# Regulators2.net
KiCad netlist of a schematic drawn in Altium Designer
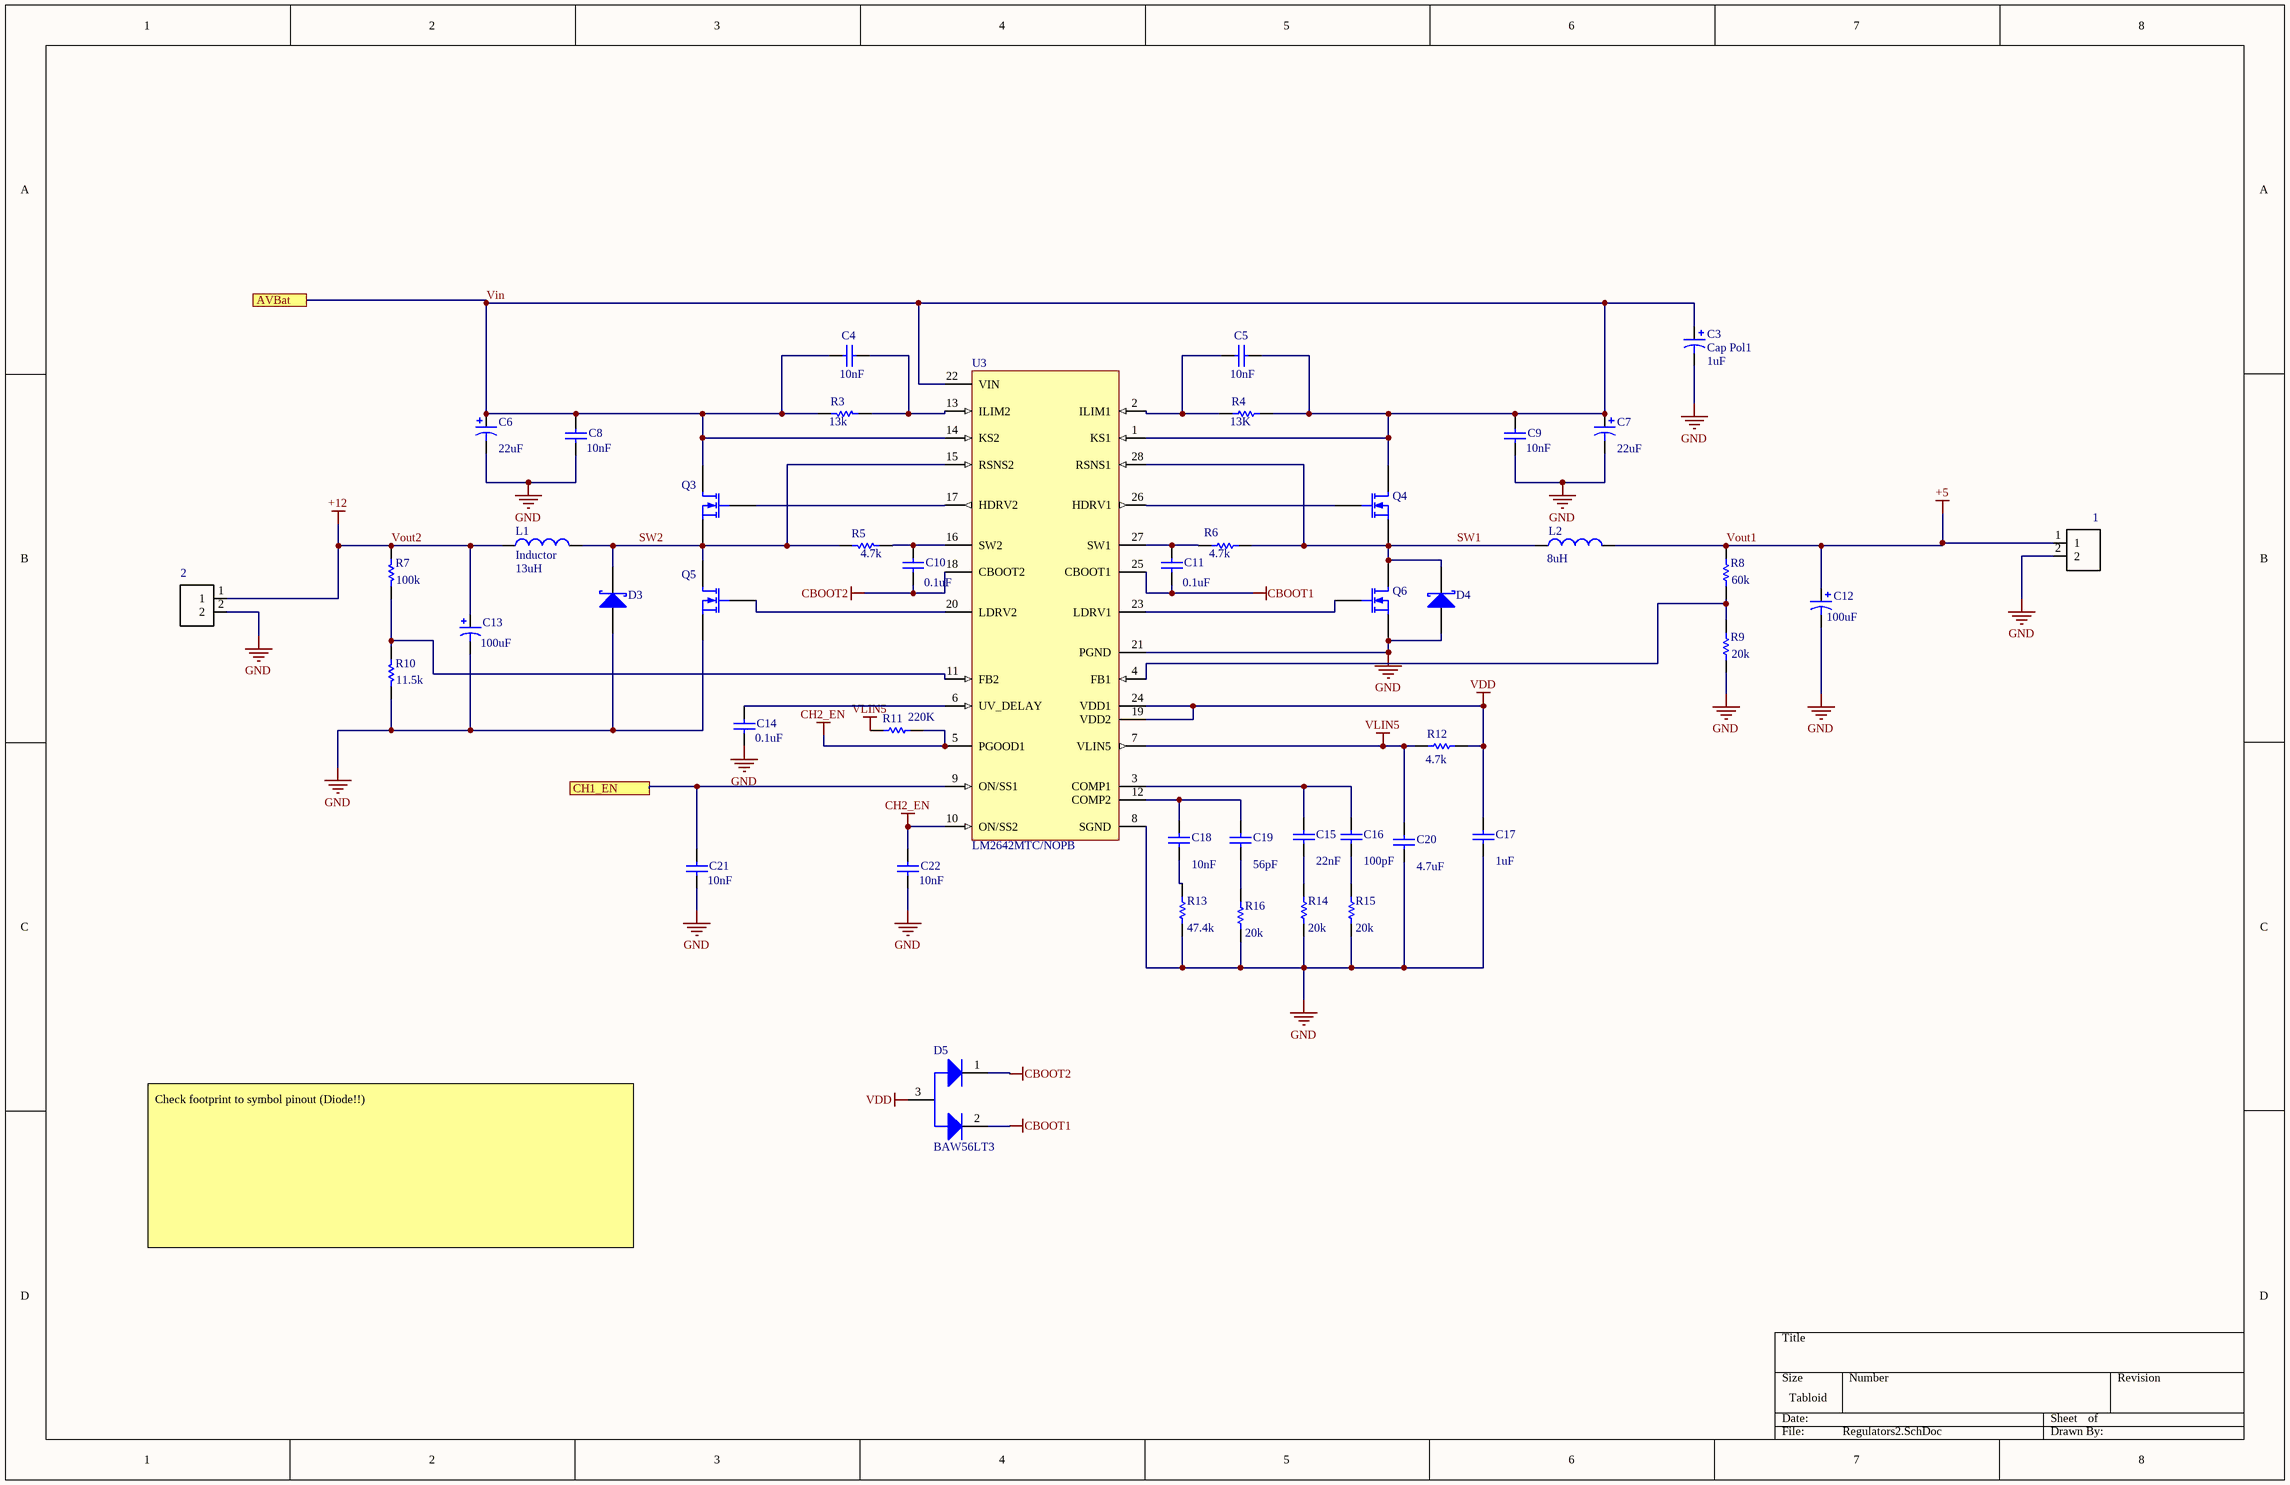
[diagram p0: Regulators2.SchDoc]

(export (version "E")
  (design (tool "Eeschema 10.0.6"))
  (components
    (comp (ref "1")
      (value "282836-2")
      (footprint "*CONN_282836-2")
      (description "Connector, Terminal Block; Wire Receptacle; 2 Pos.; 16-30 AWG; 0.197 in. CL; Sid")
      (fields (field (name "DIGI-KEY_PART_NUMBER") "A98076-ND") (field (name "MF") "TE Connectivity"))
      (libsource (lib "TerminalBlockx2") (part "282836-2"))
    )
    (comp (ref "2")
      (value "282836-2")
      (footprint "*CONN_282836-2")
      (description "Connector, Terminal Block; Wire Receptacle; 2 Pos.; 16-30 AWG; 0.197 in. CL; Sid")
      (fields (field (name "DIGI-KEY_PART_NUMBER") "A98076-ND") (field (name "MF") "TE Connectivity"))
      (libsource (lib "TerminalBlockx2") (part "282836-2"))
    )
    (comp (ref "C3")
      (value "Cap Pol1")
      (footprint "1u50VcapE")
      (description "Polarized Capacitor (Radial)")
      (fields (field (name "ALTIUM_VALUE") "1uF") (field (name "PUBLISHER") "Altium Limited"))
      (libsource (lib "") (part "Cap Pol1_1"))
    )
    (comp (ref "C4")
      (value "10nF")
      (footprint "1608[0603]")
      (description "Capacitor")
      (fields (field (name "Comment") "Cap") (field (name "PUBLISHER") "Altium Limited"))
      (libsource (lib "Miscellaneous Devices") (part "Cap"))
    )
    (comp (ref "C5")
      (value "10nF")
      (footprint "1608[0603]")
      (description "Capacitor")
      (fields (field (name "Comment") "Cap") (field (name "PUBLISHER") "Altium Limited"))
      (libsource (lib "Miscellaneous Devices") (part "Cap"))
    )
    (comp (ref "C6")
      (value "22uF")
      (footprint "22u16VcapE")
      (description "Polarized Capacitor (Radial)")
      (fields (field (name "Comment") "Cap Pol1") (field (name "PUBLISHER") "Altium Limited"))
      (libsource (lib "Miscellaneous Devices") (part "Cap Pol1"))
    )
    (comp (ref "C7")
      (value "22uF")
      (footprint "22u16VcapE")
      (description "Polarized Capacitor (Radial)")
      (fields (field (name "Comment") "Cap Pol1") (field (name "PUBLISHER") "Altium Limited"))
      (libsource (lib "") (part "Cap Pol1_1"))
    )
    (comp (ref "C8")
      (value "10nF")
      (footprint "1608[0603]")
      (description "Capacitor")
      (fields (field (name "Comment") "Cap") (field (name "PUBLISHER") "Altium Limited"))
      (libsource (lib "Miscellaneous Devices") (part "Cap"))
    )
    (comp (ref "C9")
      (value "10nF")
      (footprint "1608[0603]")
      (description "Capacitor")
      (fields (field (name "Comment") "Cap") (field (name "PUBLISHER") "Altium Limited"))
      (libsource (lib "Miscellaneous Devices") (part "Cap"))
    )
    (comp (ref "C10")
      (value "0.1uF")
      (footprint "1608[0603]")
      (description "Capacitor")
      (fields (field (name "Comment") "Cap") (field (name "PUBLISHER") "Altium Limited"))
      (libsource (lib "Miscellaneous Devices") (part "Cap"))
    )
    (comp (ref "C11")
      (value "0.1uF")
      (footprint "1608[0603]")
      (description "Capacitor")
      (fields (field (name "Comment") "Cap") (field (name "PUBLISHER") "Altium Limited"))
      (libsource (lib "Miscellaneous Devices") (part "Cap"))
    )
    (comp (ref "C12")
      (value "100uF")
      (footprint "*CAPAE660X800N")
      (description "Polarized Capacitor (Radial)")
      (fields (field (name "Comment") "Cap Pol1") (field (name "PUBLISHER") "Altium Limited"))
      (libsource (lib "") (part "Cap Pol1_1"))
    )
    (comp (ref "C13")
      (value "100uF")
      (footprint "*CAPAE660X800N")
      (description "Polarized Capacitor (Radial)")
      (fields (field (name "Comment") "Cap Pol1") (field (name "PUBLISHER") "Altium Limited"))
      (libsource (lib "Miscellaneous Devices") (part "Cap Pol1"))
    )
    (comp (ref "C14")
      (value "0.1uF")
      (footprint "1608[0603]")
      (description "Capacitor")
      (fields (field (name "Comment") "Cap") (field (name "PUBLISHER") "Altium Limited"))
      (libsource (lib "Miscellaneous Devices") (part "Cap"))
    )
    (comp (ref "C15")
      (value "22nF")
      (footprint "1608[0603]")
      (description "Capacitor")
      (fields (field (name "Comment") "Cap") (field (name "PUBLISHER") "Altium Limited"))
      (libsource (lib "Miscellaneous Devices") (part "Cap"))
    )
    (comp (ref "C16")
      (value "100pF")
      (footprint "1608[0603]")
      (description "Capacitor")
      (fields (field (name "Comment") "Cap") (field (name "PUBLISHER") "Altium Limited"))
      (libsource (lib "Miscellaneous Devices") (part "Cap"))
    )
    (comp (ref "C17")
      (value "1uF")
      (footprint "1608[0603]")
      (description "Capacitor")
      (fields (field (name "Comment") "Cap") (field (name "PUBLISHER") "Altium Limited"))
      (libsource (lib "Miscellaneous Devices") (part "Cap"))
    )
    (comp (ref "C18")
      (value "10nF")
      (footprint "1608[0603]")
      (description "Capacitor")
      (fields (field (name "Comment") "Cap") (field (name "PUBLISHER") "Altium Limited"))
      (libsource (lib "Miscellaneous Devices") (part "Cap"))
    )
    (comp (ref "C19")
      (value "56pF")
      (footprint "1608[0603]")
      (description "Capacitor")
      (fields (field (name "Comment") "Cap") (field (name "PUBLISHER") "Altium Limited"))
      (libsource (lib "Miscellaneous Devices") (part "Cap"))
    )
    (comp (ref "C20")
      (value "4.7uF")
      (footprint "1608[0603]")
      (description "Capacitor")
      (fields (field (name "Comment") "Cap") (field (name "PUBLISHER") "Altium Limited"))
      (libsource (lib "Miscellaneous Devices") (part "Cap"))
    )
    (comp (ref "C21")
      (value "10nF")
      (footprint "1608[0603]")
      (description "Capacitor")
      (fields (field (name "Comment") "Cap") (field (name "PUBLISHER") "Altium Limited"))
      (libsource (lib "Miscellaneous Devices") (part "Cap"))
    )
    (comp (ref "C22")
      (value "10nF")
      (footprint "1608[0603]")
      (description "Capacitor")
      (fields (field (name "Comment") "Cap") (field (name "PUBLISHER") "Altium Limited"))
      (libsource (lib "Miscellaneous Devices") (part "Cap"))
    )
    (comp (ref "D3")
      (value "Diode MBRS140t3")
      (footprint "*DIOM5227X270N_S1M(Primary)")
      (description "Schottky Rectifier")
      (fields (field (name "PUBLISHER") "Altium Limited"))
      (libsource (lib "Miscellaneous Devices") (part "Diode 18TQ045"))
    )
    (comp (ref "D4")
      (value "Diode MBRS140t3")
      (footprint "*DIOM5227X270N_S1M(Primary)")
      (description "Schottky Rectifier")
      (fields (field (name "PUBLISHER") "Altium Limited"))
      (libsource (lib "Miscellaneous Devices") (part "Diode 18TQ045"))
    )
    (comp (ref "D5")
      (value "BAW56LT3")
      (footprint "ONSC-SOT-23-3-318-08_V")
      (description "Dual Switching Diodes, Common Anode, 3-Pin SOT-23, Tape and Reel")
      (fields (field (name "MANUFACTURER") "On Semiconductor"))
      (libsource (lib "ON Semi Small Signal Switching Diodes") (part "BAW56LT3"))
    )
    (comp (ref "L1")
      (value "Inductor")
      (footprint "Inductor")
      (fields (field (name "ALTIUM_VALUE") "13uH") (field (name "PUBLISHER") "Altium Limited"))
      (libsource (lib "Miscellaneous Devices") (part "Inductor"))
    )
    (comp (ref "L2")
      (value "8uH")
      (footprint "Inductor")
      (description "Inductor")
      (fields (field (name "PUBLISHER") "Altium Limited"))
      (libsource (lib "Miscellaneous Devices") (part "Inductor"))
    )
    (comp (ref "Q3")
      (value "MOSFET-N")
      (footprint "SO8_L")
      (description "N-Channel MOSFET")
      (fields (field (name "PUBLISHER") "Altium Limited"))
      (libsource (lib "Miscellaneous Devices") (part "MOSFET-N"))
    )
    (comp (ref "Q4")
      (value "MOSFET-N")
      (footprint "SO8_L")
      (description "N-Channel MOSFET")
      (fields (field (name "PUBLISHER") "Altium Limited"))
      (libsource (lib "Miscellaneous Devices") (part "MOSFET-N"))
    )
    (comp (ref "Q5")
      (value "MOSFET-N")
      (footprint "SO8_L")
      (description "N-Channel MOSFET")
      (fields (field (name "PUBLISHER") "Altium Limited"))
      (libsource (lib "Miscellaneous Devices") (part "MOSFET-N"))
    )
    (comp (ref "Q6")
      (value "MOSFET-N")
      (footprint "SO8_L")
      (description "N-Channel MOSFET")
      (fields (field (name "PUBLISHER") "Altium Limited"))
      (libsource (lib "Miscellaneous Devices") (part "MOSFET-N"))
    )
    (comp (ref "R3")
      (value "13k")
      (footprint "1608[0603]")
      (description "Resistor")
      (fields (field (name "Comment") "Res1") (field (name "PUBLISHER") "Altium Limited"))
      (libsource (lib "Miscellaneous Devices") (part "Res1"))
    )
    (comp (ref "R4")
      (value "13K")
      (footprint "1608[0603]")
      (description "Resistor")
      (fields (field (name "Comment") "Res1") (field (name "PUBLISHER") "Altium Limited"))
      (libsource (lib "Miscellaneous Devices") (part "Res1"))
    )
    (comp (ref "R5")
      (value "4.7k")
      (footprint "1608[0603]")
      (description "Resistor")
      (fields (field (name "Comment") "Res1") (field (name "PUBLISHER") "Altium Limited"))
      (libsource (lib "Miscellaneous Devices") (part "Res1"))
    )
    (comp (ref "R6")
      (value "4.7k")
      (footprint "1608[0603]")
      (description "Resistor")
      (fields (field (name "Comment") "Res1") (field (name "PUBLISHER") "Altium Limited"))
      (libsource (lib "Miscellaneous Devices") (part "Res1"))
    )
    (comp (ref "R7")
      (value "100k")
      (footprint "1608[0603]")
      (description "Resistor")
      (fields (field (name "Comment") "Res1") (field (name "PUBLISHER") "Altium Limited"))
      (libsource (lib "Miscellaneous Devices") (part "Res1"))
    )
    (comp (ref "R8")
      (value "60k")
      (footprint "1608[0603]")
      (description "Resistor")
      (fields (field (name "Comment") "Res1") (field (name "PUBLISHER") "Altium Limited"))
      (libsource (lib "Miscellaneous Devices") (part "Res1"))
    )
    (comp (ref "R9")
      (value "20k")
      (footprint "1608[0603]")
      (description "Resistor")
      (fields (field (name "Comment") "Res1") (field (name "PUBLISHER") "Altium Limited"))
      (libsource (lib "Miscellaneous Devices") (part "Res1"))
    )
    (comp (ref "R10")
      (value "11.5k")
      (footprint "1608[0603]")
      (description "Resistor")
      (fields (field (name "Comment") "Res1") (field (name "PUBLISHER") "Altium Limited"))
      (libsource (lib "Miscellaneous Devices") (part "Res1"))
    )
    (comp (ref "R11")
      (value "220K")
      (footprint "1608[0603]")
      (description "Resistor")
      (fields (field (name "Comment") "Res1") (field (name "PUBLISHER") "Altium Limited"))
      (libsource (lib "Miscellaneous Devices") (part "Res1"))
    )
    (comp (ref "R12")
      (value "4.7k")
      (footprint "1608[0603]")
      (description "Resistor")
      (fields (field (name "Comment") "Res1") (field (name "PUBLISHER") "Altium Limited"))
      (libsource (lib "Miscellaneous Devices") (part "Res1"))
    )
    (comp (ref "R13")
      (value "47.4k")
      (footprint "1608[0603]")
      (description "Resistor")
      (fields (field (name "Comment") "Res1") (field (name "PUBLISHER") "Altium Limited"))
      (libsource (lib "Miscellaneous Devices") (part "Res1"))
    )
    (comp (ref "R14")
      (value "20k")
      (footprint "1608[0603]")
      (description "Resistor")
      (fields (field (name "Comment") "Res1") (field (name "PUBLISHER") "Altium Limited"))
      (libsource (lib "Miscellaneous Devices") (part "Res1"))
    )
    (comp (ref "R15")
      (value "20k")
      (footprint "1608[0603]")
      (description "Resistor")
      (fields (field (name "Comment") "Res1") (field (name "PUBLISHER") "Altium Limited"))
      (libsource (lib "Miscellaneous Devices") (part "Res1"))
    )
    (comp (ref "R16")
      (value "20k")
      (footprint "1608[0603]")
      (description "Resistor")
      (fields (field (name "Comment") "Res1") (field (name "PUBLISHER") "Altium Limited"))
      (libsource (lib "Miscellaneous Devices") (part "Res1"))
    )
    (comp (ref "U3")
      (value "LM2642MTC/NOPB")
      (footprint "MTC28_N")
      (description "Two-Phase Synchronous Step-Down Switching Controller, 28-pin TSSOP, Pb-Free")
      (fields (field (name "MANUFACTURER") "National Semiconductor"))
      (libsource (lib "National Semiconductor Switcher") (part "LM2642MTC/NOPB"))
    )
  )
  (nets
    (net (code "1") (name "+5") (class "Default")
      (node (ref "1") (pin "1") (pinfunction "1_1") (pintype "passive"))
      (node (ref "C12") (pin "1") (pinfunction "1_1") (pintype "passive"))
      (node (ref "L2") (pin "2") (pinfunction "2_2") (pintype "passive"))
      (node (ref "R8") (pin "2") (pinfunction "2_2") (pintype "passive"))
    )
    (net (code "2") (name "+12") (class "Default")
      (node (ref "2") (pin "1") (pinfunction "1_1") (pintype "passive"))
      (node (ref "C13") (pin "1") (pinfunction "1_1") (pintype "passive"))
      (node (ref "L1") (pin "1") (pinfunction "1_1") (pintype "passive"))
      (node (ref "R7") (pin "2") (pinfunction "2_2") (pintype "passive"))
    )
    (net (code "3") (name "/CH1_EN") (class "Default")
      (node (ref "C21") (pin "2") (pinfunction "2_2") (pintype "passive"))
      (node (ref "U3") (pin "9") (pinfunction "ON/SS1_9") (pintype "input"))
    )
    (net (code "4") (name "/SW1") (class "Default")
      (node (ref "D4") (pin "1") (pinfunction "K_1") (pintype "passive"))
      (node (ref "L2") (pin "1") (pinfunction "1_1") (pintype "passive"))
      (node (ref "Q4") (pin "3") (pinfunction "S_3") (pintype "passive"))
      (node (ref "Q6") (pin "1") (pinfunction "D_1") (pintype "passive"))
      (node (ref "R6") (pin "2") (pinfunction "2_2") (pintype "passive"))
      (node (ref "U3") (pin "28") (pinfunction "RSNS1_28") (pintype "input"))
    )
    (net (code "5") (name "/SW2") (class "Default")
      (node (ref "D3") (pin "1") (pinfunction "K_1") (pintype "passive"))
      (node (ref "L1") (pin "2") (pinfunction "2_2") (pintype "passive"))
      (node (ref "Q3") (pin "3") (pinfunction "S_3") (pintype "passive"))
      (node (ref "Q5") (pin "1") (pinfunction "D_1") (pintype "passive"))
      (node (ref "R5") (pin "2") (pinfunction "2_2") (pintype "passive"))
      (node (ref "U3") (pin "15") (pinfunction "RSNS2_15") (pintype "input"))
    )
    (net (code "6") (name "/Vin") (class "Default")
      (node (ref "C3") (pin "1") (pinfunction "1_1") (pintype "passive"))
      (node (ref "C4") (pin "2") (pinfunction "2_2") (pintype "passive"))
      (node (ref "C5") (pin "2") (pinfunction "2_2") (pintype "passive"))
      (node (ref "C6") (pin "1") (pinfunction "1_1") (pintype "passive"))
      (node (ref "C7") (pin "1") (pinfunction "1_1") (pintype "passive"))
      (node (ref "C8") (pin "2") (pinfunction "2_2") (pintype "passive"))
      (node (ref "C9") (pin "2") (pinfunction "2_2") (pintype "passive"))
      (node (ref "Q3") (pin "1") (pinfunction "D_1") (pintype "passive"))
      (node (ref "Q4") (pin "1") (pinfunction "D_1") (pintype "passive"))
      (node (ref "R3") (pin "2") (pinfunction "2_2") (pintype "passive"))
      (node (ref "R4") (pin "2") (pinfunction "2_2") (pintype "passive"))
      (node (ref "U3") (pin "1") (pinfunction "KS1_1") (pintype "input"))
      (node (ref "U3") (pin "14") (pinfunction "KS2_14") (pintype "input"))
      (node (ref "U3") (pin "22") (pinfunction "VIN_22") (pintype "power_in"))
    )
    (net (code "7") (name "CBOOT1") (class "Default")
      (node (ref "C11") (pin "1") (pinfunction "1_1") (pintype "passive"))
      (node (ref "D5") (pin "2") (pinfunction "K2_2") (pintype "passive"))
      (node (ref "U3") (pin "25") (pinfunction "CBOOT1_25") (pintype "passive"))
    )
    (net (code "8") (name "CBOOT2") (class "Default")
      (node (ref "C10") (pin "1") (pinfunction "1_1") (pintype "passive"))
      (node (ref "D5") (pin "1") (pinfunction "K1_1") (pintype "passive"))
      (node (ref "U3") (pin "18") (pinfunction "CBOOT2_18") (pintype "passive"))
    )
    (net (code "9") (name "CH2_EN") (class "Default")
      (node (ref "C22") (pin "2") (pinfunction "2_2") (pintype "passive"))
      (node (ref "R11") (pin "2") (pinfunction "2_2") (pintype "passive"))
      (node (ref "U3") (pin "10") (pinfunction "ON/SS2_10") (pintype "input"))
      (node (ref "U3") (pin "5") (pinfunction "PGOOD1_5") (pintype "open_collector"))
    )
    (net (code "10") (name "GND") (class "Default")
      (node (ref "1") (pin "2") (pinfunction "2_2") (pintype "passive"))
      (node (ref "2") (pin "2") (pinfunction "2_2") (pintype "passive"))
      (node (ref "C12") (pin "2") (pinfunction "2_2") (pintype "passive"))
      (node (ref "C13") (pin "2") (pinfunction "2_2") (pintype "passive"))
      (node (ref "C14") (pin "1") (pinfunction "1_1") (pintype "passive"))
      (node (ref "C17") (pin "1") (pinfunction "1_1") (pintype "passive"))
      (node (ref "C20") (pin "1") (pinfunction "1_1") (pintype "passive"))
      (node (ref "C21") (pin "1") (pinfunction "1_1") (pintype "passive"))
      (node (ref "C22") (pin "1") (pinfunction "1_1") (pintype "passive"))
      (node (ref "C3") (pin "2") (pinfunction "2_2") (pintype "passive"))
      (node (ref "C6") (pin "2") (pinfunction "2_2") (pintype "passive"))
      (node (ref "C7") (pin "2") (pinfunction "2_2") (pintype "passive"))
      (node (ref "C8") (pin "1") (pinfunction "1_1") (pintype "passive"))
      (node (ref "C9") (pin "1") (pinfunction "1_1") (pintype "passive"))
      (node (ref "D3") (pin "3") (pinfunction "A_3") (pintype "passive"))
      (node (ref "D4") (pin "3") (pinfunction "A_3") (pintype "passive"))
      (node (ref "Q5") (pin "3") (pinfunction "S_3") (pintype "passive"))
      (node (ref "Q6") (pin "3") (pinfunction "S_3") (pintype "passive"))
      (node (ref "R10") (pin "1") (pinfunction "1_1") (pintype "passive"))
      (node (ref "R13") (pin "1") (pinfunction "1_1") (pintype "passive"))
      (node (ref "R14") (pin "1") (pinfunction "1_1") (pintype "passive"))
      (node (ref "R15") (pin "1") (pinfunction "1_1") (pintype "passive"))
      (node (ref "R16") (pin "1") (pinfunction "1_1") (pintype "passive"))
      (node (ref "R9") (pin "1") (pinfunction "1_1") (pintype "passive"))
      (node (ref "U3") (pin "21") (pinfunction "PGND_21") (pintype "power_in"))
      (node (ref "U3") (pin "8") (pinfunction "SGND_8") (pintype "power_in"))
    )
    (net (code "11") (name "Net-(C15-Pad1)") (class "Default")
      (node (ref "C15") (pin "1") (pinfunction "1_1") (pintype "passive"))
      (node (ref "R14") (pin "2") (pinfunction "2_2") (pintype "passive"))
    )
    (net (code "12") (name "Net-(C16-Pad1)") (class "Default")
      (node (ref "C16") (pin "1") (pinfunction "1_1") (pintype "passive"))
      (node (ref "R15") (pin "2") (pinfunction "2_2") (pintype "passive"))
    )
    (net (code "13") (name "Net-(C18-Pad1)") (class "Default")
      (node (ref "C18") (pin "1") (pinfunction "1_1") (pintype "passive"))
      (node (ref "R13") (pin "2") (pinfunction "2_2") (pintype "passive"))
    )
    (net (code "14") (name "Net-(C19-Pad1)") (class "Default")
      (node (ref "C19") (pin "1") (pinfunction "1_1") (pintype "passive"))
      (node (ref "R16") (pin "2") (pinfunction "2_2") (pintype "passive"))
    )
    (net (code "15") (name "Net-(Q3-G)") (class "Default")
      (node (ref "Q3") (pin "2") (pinfunction "G_2") (pintype "passive"))
      (node (ref "U3") (pin "17") (pinfunction "HDRV2_17") (pintype "output"))
    )
    (net (code "16") (name "Net-(Q4-G)") (class "Default")
      (node (ref "Q4") (pin "2") (pinfunction "G_2") (pintype "passive"))
      (node (ref "U3") (pin "26") (pinfunction "HDRV1_26") (pintype "output"))
    )
    (net (code "17") (name "Net-(Q5-G)") (class "Default")
      (node (ref "Q5") (pin "2") (pinfunction "G_2") (pintype "passive"))
      (node (ref "U3") (pin "20") (pinfunction "LDRV2_20") (pintype "power_in"))
    )
    (net (code "18") (name "Net-(Q6-G)") (class "Default")
      (node (ref "Q6") (pin "2") (pinfunction "G_2") (pintype "passive"))
      (node (ref "U3") (pin "23") (pinfunction "LDRV1_23") (pintype "power_in"))
    )
    (net (code "19") (name "Net-(U3-COMP1)") (class "Default")
      (node (ref "C15") (pin "2") (pinfunction "2_2") (pintype "passive"))
      (node (ref "C16") (pin "2") (pinfunction "2_2") (pintype "passive"))
      (node (ref "U3") (pin "3") (pinfunction "COMP1_3") (pintype "passive"))
    )
    (net (code "20") (name "Net-(U3-COMP2)") (class "Default")
      (node (ref "C18") (pin "2") (pinfunction "2_2") (pintype "passive"))
      (node (ref "C19") (pin "2") (pinfunction "2_2") (pintype "passive"))
      (node (ref "U3") (pin "12") (pinfunction "COMP2_12") (pintype "passive"))
    )
    (net (code "21") (name "Net-(U3-FB1)") (class "Default")
      (node (ref "R8") (pin "1") (pinfunction "1_1") (pintype "passive"))
      (node (ref "R9") (pin "2") (pinfunction "2_2") (pintype "passive"))
      (node (ref "U3") (pin "4") (pinfunction "FB1_4") (pintype "input"))
    )
    (net (code "22") (name "Net-(U3-FB2)") (class "Default")
      (node (ref "R10") (pin "2") (pinfunction "2_2") (pintype "passive"))
      (node (ref "R7") (pin "1") (pinfunction "1_1") (pintype "passive"))
      (node (ref "U3") (pin "11") (pinfunction "FB2_11") (pintype "input"))
    )
    (net (code "23") (name "Net-(U3-ILIM1)") (class "Default")
      (node (ref "C5") (pin "1") (pinfunction "1_1") (pintype "passive"))
      (node (ref "R4") (pin "1") (pinfunction "1_1") (pintype "passive"))
      (node (ref "U3") (pin "2") (pinfunction "ILIM1_2") (pintype "input"))
    )
    (net (code "24") (name "Net-(U3-ILIM2)") (class "Default")
      (node (ref "C4") (pin "1") (pinfunction "1_1") (pintype "passive"))
      (node (ref "R3") (pin "1") (pinfunction "1_1") (pintype "passive"))
      (node (ref "U3") (pin "13") (pinfunction "ILIM2_13") (pintype "input"))
    )
    (net (code "25") (name "Net-(U3-SW1)") (class "Default")
      (node (ref "C11") (pin "2") (pinfunction "2_2") (pintype "passive"))
      (node (ref "R6") (pin "1") (pinfunction "1_1") (pintype "passive"))
      (node (ref "U3") (pin "27") (pinfunction "SW1_27") (pintype "power_in"))
    )
    (net (code "26") (name "Net-(U3-SW2)") (class "Default")
      (node (ref "C10") (pin "2") (pinfunction "2_2") (pintype "passive"))
      (node (ref "R5") (pin "1") (pinfunction "1_1") (pintype "passive"))
      (node (ref "U3") (pin "16") (pinfunction "SW2_16") (pintype "power_in"))
    )
    (net (code "27") (name "Net-(U3-UV_DELAY)") (class "Default")
      (node (ref "C14") (pin "2") (pinfunction "2_2") (pintype "passive"))
      (node (ref "U3") (pin "6") (pinfunction "UV_DELAY_6") (pintype "input"))
    )
    (net (code "28") (name "VDD") (class "Default")
      (node (ref "C17") (pin "2") (pinfunction "2_2") (pintype "passive"))
      (node (ref "D5") (pin "3") (pinfunction "A_3") (pintype "passive"))
      (node (ref "R12") (pin "2") (pinfunction "2_2") (pintype "passive"))
      (node (ref "U3") (pin "19") (pinfunction "VDD2_19") (pintype "power_in"))
      (node (ref "U3") (pin "24") (pinfunction "VDD1_24") (pintype "power_in"))
    )
    (net (code "29") (name "VLIN5") (class "Default")
      (node (ref "C20") (pin "2") (pinfunction "2_2") (pintype "passive"))
      (node (ref "R11") (pin "1") (pinfunction "1_1") (pintype "passive"))
      (node (ref "R12") (pin "1") (pinfunction "1_1") (pintype "passive"))
      (node (ref "U3") (pin "7") (pinfunction "VLIN5_7") (pintype "output"))
    )
  )
)
